# LED_DRV.net
KiCad netlist of a schematic drawn in Altium Designer
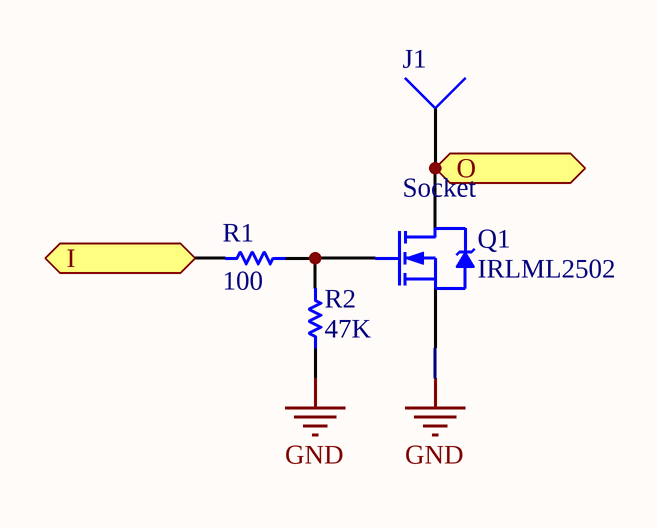
[diagram p0: LED_DRV.SchDoc]

(export (version "E")
  (design (tool "Eeschema 10.0.6"))
  (components
    (comp (ref "J1")
      (value "Socket")
      (footprint "PIN#001")
      (fields (field (name "PUBLISHER") "Altium Limited"))
      (libsource (lib "Miscellaneous Connectors") (part "Socket"))
    )
    (comp (ref "Q1")
      (value "IRLML2502")
      (footprint "SOT-23_N")
      (description "HEXFET Power MOSFET")
      (fields (field (name "PUBLISHER") "Altium Limited"))
      (libsource (lib "IR Discrete MOSFET - Power") (part "IRLML2402"))
    )
    (comp (ref "R1")
      (value "100")
      (footprint "0603x")
      (description "Resistor")
      (fields (field (name "PUBLISHER") "Altium Limited"))
      (libsource (lib "Miscellaneous Devices") (part "Res1"))
    )
    (comp (ref "R2")
      (value "47K")
      (footprint "0603x")
      (description "Resistor")
      (fields (field (name "PUBLISHER") "Altium Limited"))
      (libsource (lib "Miscellaneous Devices") (part "Res1"))
    )
  )
  (nets
    (net (code "1") (name "/I") (class "Default")
      (node (ref "R1") (pin "2") (pinfunction "2_2") (pintype "passive"))
    )
    (net (code "2") (name "/O") (class "Default")
      (node (ref "J1") (pin "1") (pinfunction "1_1") (pintype "passive"))
      (node (ref "Q1") (pin "3") (pinfunction "D_3") (pintype "passive"))
    )
    (net (code "3") (name "GND") (class "Default")
      (node (ref "Q1") (pin "2") (pinfunction "S_2") (pintype "passive"))
      (node (ref "R2") (pin "1") (pinfunction "1_1") (pintype "passive"))
    )
    (net (code "4") (name "Net-(Q1-G)") (class "Default")
      (node (ref "Q1") (pin "1") (pinfunction "G_1") (pintype "passive"))
      (node (ref "R1") (pin "1") (pinfunction "1_1") (pintype "passive"))
      (node (ref "R2") (pin "2") (pinfunction "2_2") (pintype "passive"))
    )
  )
)
